# MCP3421_adapter.net
KiCad netlist of a schematic drawn in EAGLE
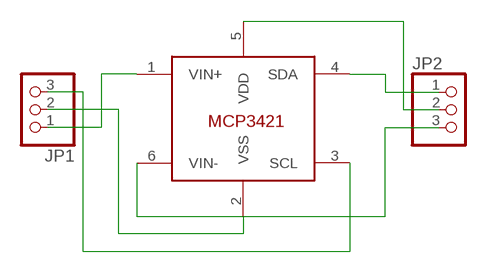
[diagram p0: schematic, sheet 1]

(export (version "E")
  (design (tool "Eeschema 10.0.6"))
  (components
    (comp (ref "JP1")
      (value "PINHD-1X3")
      (footprint "eagle-import:1X03")
      (libsource (lib "eagle-import") (part "PINHD-1X3"))
    )
    (comp (ref "JP2")
      (value "PINHD-1X3")
      (footprint "eagle-import:1X03")
      (libsource (lib "eagle-import") (part "PINHD-1X3"))
    )
    (comp (ref "U$1")
      (value "MCP3421")
      (footprint "eagle-import:SOT23-6")
      (libsource (lib "eagle-import") (part "MCP3421"))
    )
  )
  (nets
    (net (code "1") (name "Net-(U$1-SCL)") (class "Default")
      (node (ref "JP1") (pin "3") (pinfunction "3_3") (pintype "passive"))
      (node (ref "U$1") (pin "3") (pinfunction "SCL_3") (pintype "bidirectional"))
    )
    (net (code "2") (name "Net-(U$1-SDA)") (class "Default")
      (node (ref "JP2") (pin "1") (pinfunction "1_1") (pintype "passive"))
      (node (ref "U$1") (pin "4") (pinfunction "SDA_4") (pintype "bidirectional"))
    )
    (net (code "3") (name "Net-(U$1-VDD)") (class "Default")
      (node (ref "JP2") (pin "2") (pinfunction "2_2") (pintype "passive"))
      (node (ref "U$1") (pin "5") (pinfunction "VDD_5") (pintype "bidirectional"))
    )
    (net (code "4") (name "Net-(U$1-VIN+)") (class "Default")
      (node (ref "JP1") (pin "1") (pinfunction "1_1") (pintype "passive"))
      (node (ref "U$1") (pin "1") (pinfunction "VIN+_1") (pintype "bidirectional"))
    )
    (net (code "5") (name "Net-(U$1-VIN-)") (class "Default")
      (node (ref "JP2") (pin "3") (pinfunction "3_3") (pintype "passive"))
      (node (ref "U$1") (pin "6") (pinfunction "VIN-_6") (pintype "bidirectional"))
    )
    (net (code "6") (name "Net-(U$1-VSS)") (class "Default")
      (node (ref "JP1") (pin "2") (pinfunction "2_2") (pintype "passive"))
      (node (ref "U$1") (pin "2") (pinfunction "VSS_2") (pintype "bidirectional"))
    )
  )
)
